# gnd_kond.net
KiCad netlist of a schematic drawn in EAGLE
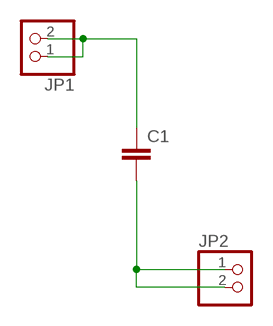
[diagram p0: schematic, sheet 1]

(export (version "E")
  (design (tool "Eeschema 10.0.6"))
  (components
    (comp (ref "C1")
      (value "C-EU150-091X182")
      (footprint "eagle-import:C150-091X182")
      (libsource (lib "eagle-import") (part "C-EU150-091X182"))
    )
    (comp (ref "JP1")
      (value "PINHD-1X2")
      (footprint "eagle-import:1X02")
      (libsource (lib "eagle-import") (part "PINHD-1X2"))
    )
    (comp (ref "JP2")
      (value "PINHD-1X2")
      (footprint "eagle-import:1X02")
      (libsource (lib "eagle-import") (part "PINHD-1X2"))
    )
  )
  (nets
    (net (code "1") (name "Net-(C1-Pad1)") (class "Default")
      (node (ref "C1") (pin "1") (pinfunction "1_1") (pintype "passive"))
      (node (ref "JP1") (pin "1") (pinfunction "1_1") (pintype "passive"))
      (node (ref "JP1") (pin "2") (pinfunction "2_2") (pintype "passive"))
    )
    (net (code "2") (name "Net-(C1-Pad2)") (class "Default")
      (node (ref "C1") (pin "2") (pinfunction "2_2") (pintype "passive"))
      (node (ref "JP2") (pin "1") (pinfunction "1_1") (pintype "passive"))
      (node (ref "JP2") (pin "2") (pinfunction "2_2") (pintype "passive"))
    )
  )
)
